# FanoutTest.net
KiCad netlist of a schematic drawn in Altium Designer
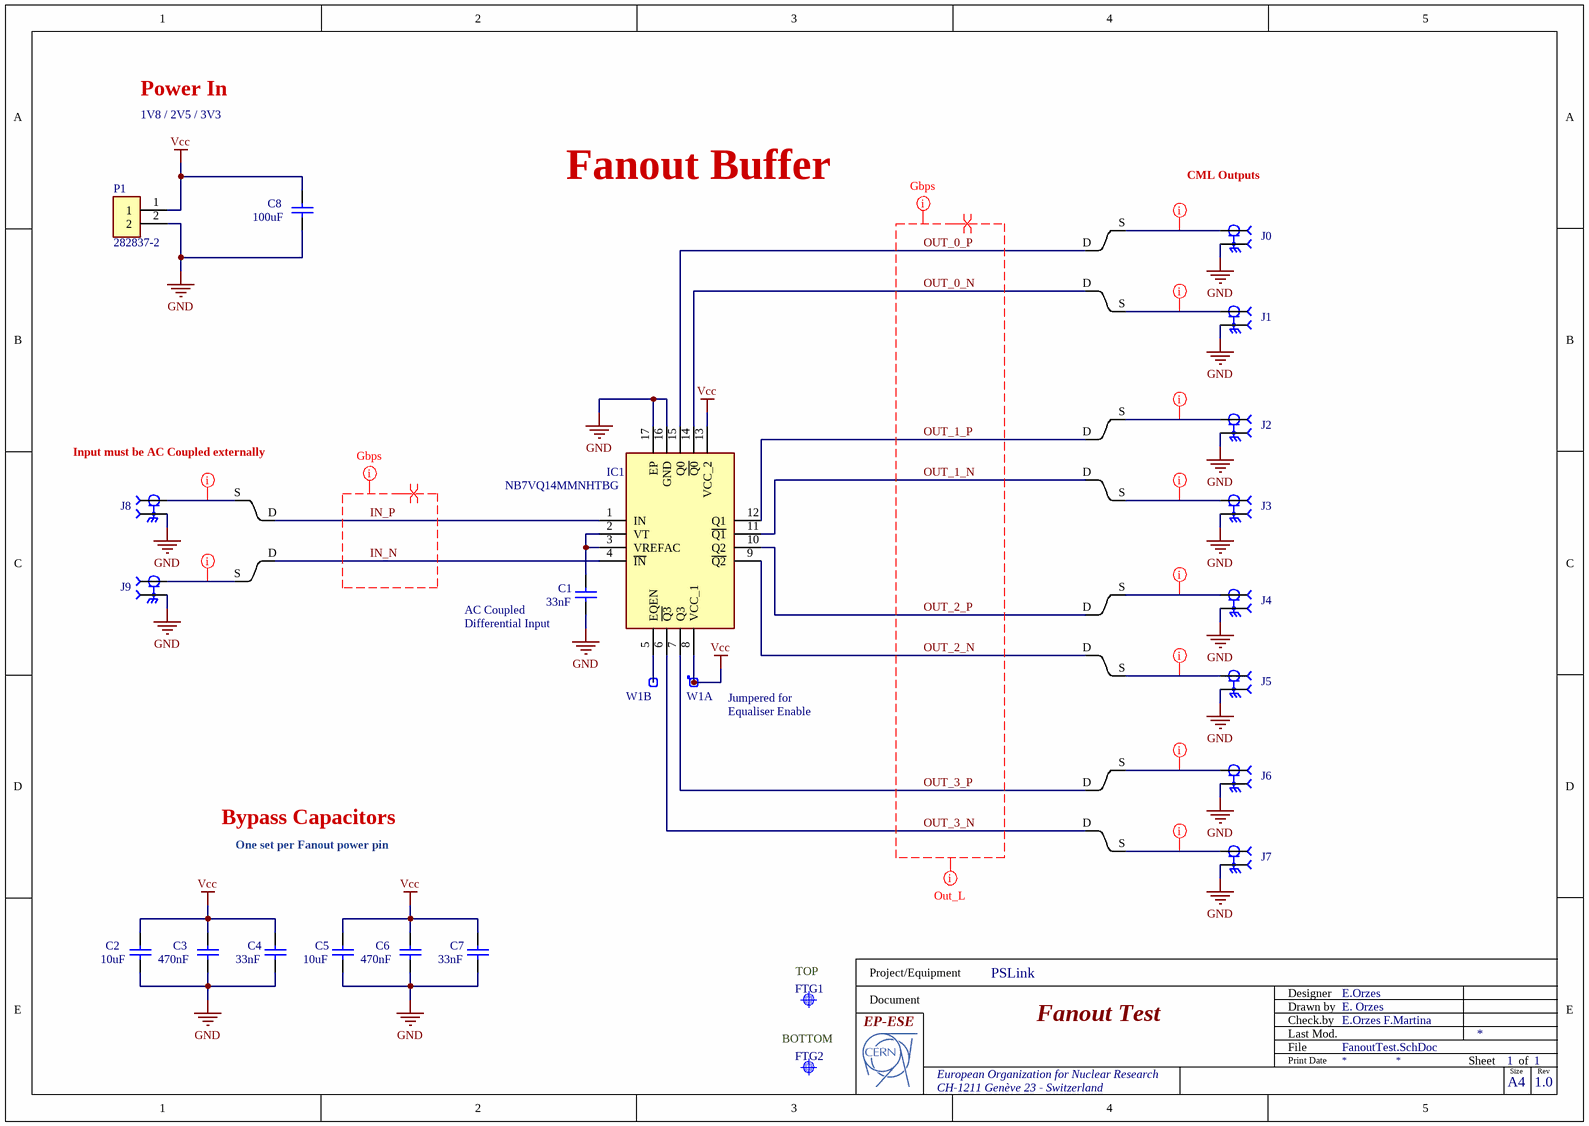
[diagram p0: FanoutTest.SchDoc]

(export (version "E")
  (design (tool "Eeschema 10.0.6"))
  (components
    (comp (ref "C1")
      (value "33nF")
      (footprint "LLL03TR61E333KE01")
      (description "LLL03TR61E333KE01")
      (libsource (lib "auxiliary_library") (part "Capacitor - non polarized"))
    )
    (comp (ref "C2")
      (value "10uF")
      (footprint "CAPC1608X87N")
      (description "GRM188D71A106KA73")
      (fields
        (field (name "PART NUMBER") "CC0603_10UF_6.3V_20%_X5R")
        (field (name "VOLTAGE") "6.3V")
        (field (name "AUTHOR") "CERN DEM JLC")
      )
      (libsource (lib "Capacitors") (part "Capacitor - non polarized"))
    )
    (comp (ref "C3")
      (value "470nF")
      (footprint "CAPC0510X04N")
      (description "LLL153C70G474ME17")
      (libsource (lib "auxiliary_library") (part "Capacitor - non polarized"))
    )
    (comp (ref "C4")
      (value "33nF")
      (footprint "LLL03TR61E333KE01")
      (description "LLL03TR61E333KE01")
      (libsource (lib "auxiliary_library") (part "Capacitor - non polarized"))
    )
    (comp (ref "C5")
      (value "10uF")
      (footprint "CAPC1608X87N")
      (description "GRM188D71A106KA73")
      (fields
        (field (name "PART NUMBER") "CC0603_10UF_6.3V_20%_X5R")
        (field (name "VOLTAGE") "6.3V")
        (field (name "AUTHOR") "CERN DEM JLC")
      )
      (libsource (lib "Capacitors") (part "Capacitor - non polarized"))
    )
    (comp (ref "C6")
      (value "470nF")
      (footprint "CAPC0510X04N")
      (description "LLL153C70G474ME17")
      (libsource (lib "auxiliary_library") (part "Capacitor - non polarized"))
    )
    (comp (ref "C7")
      (value "33nF")
      (footprint "LLL03TR61E333KE01")
      (description "LLL03TR61E333KE01")
      (libsource (lib "auxiliary_library") (part "Capacitor - non polarized"))
    )
    (comp (ref "C8")
      (value "100uF")
      (footprint "CAPC3225X270N")
      (description "GRM32EC70J107ME15")
      (fields
        (field (name "PART NUMBER") "CC1210_100UF_6.3V_20%_X7U")
        (field (name "VOLTAGE") "6.3V")
        (field (name "AUTHOR") "CERN DEM MR")
      )
      (libsource (lib "Capacitors") (part "Capacitor - non polarized"))
    )
    (comp (ref "FTG1")
      (value "Use only in PCB")
      (footprint "FIDUCIAL_TOP_C100-200")
      (description "Fiducial Target")
      (fields (field (name "PART NUMBER") "FIDUCIAL_TARGET_C100-200") (field (name "AUTHOR") "CERN DEM JLC"))
      (libsource (lib "Eletro-mechanical") (part "Fiducial Target"))
    )
    (comp (ref "FTG2")
      (value "Use only in PCB")
      (footprint "FIDUCIAL_TOP_C100-200")
      (description "Fiducial Target")
      (fields (field (name "PART NUMBER") "FIDUCIAL_TARGET_C100-200") (field (name "AUTHOR") "CERN DEM JLC"))
      (libsource (lib "Eletro-mechanical") (part "Fiducial Target"))
    )
    (comp (ref "IC1")
      (value "NB7VQ14MMNHTBG")
      (footprint "SamacSys:QFN50P300X300X100-17N")
      (description "Integrated Circuit")
      (fields (field (name "MOUSER PART NUMBER") "863-NB7VQ14MMNHTBG"))
      (libsource (lib "*") (part "NB7VQ14MMNHTBG"))
    )
    (comp (ref "J0") (value "SMA") (footprint "CONSMA022-G") (libsource (lib "CONSMA022-G") (part "SMA")))
    (comp (ref "J1") (value "SMA") (footprint "CONSMA022-G") (libsource (lib "CONSMA022-G") (part "SMA")))
    (comp (ref "J2") (value "SMA") (footprint "CONSMA022-G") (libsource (lib "CONSMA022-G") (part "SMA")))
    (comp (ref "J3") (value "SMA") (footprint "CONSMA022-G") (libsource (lib "CONSMA022-G") (part "SMA")))
    (comp (ref "J4") (value "SMA") (footprint "CONSMA022-G") (libsource (lib "CONSMA022-G") (part "SMA")))
    (comp (ref "J5") (value "SMA") (footprint "CONSMA022-G") (libsource (lib "CONSMA022-G") (part "SMA")))
    (comp (ref "J6") (value "SMA") (footprint "CONSMA022-G") (libsource (lib "CONSMA022-G") (part "SMA")))
    (comp (ref "J7") (value "SMA") (footprint "CONSMA022-G") (libsource (lib "CONSMA022-G") (part "SMA")))
    (comp (ref "J8") (value "SMA") (footprint "CONSMA022-G") (libsource (lib "CONSMA022-G") (part "SMA")))
    (comp (ref "J9") (value "SMA") (footprint "CONSMA022-G") (libsource (lib "CONSMA022-G") (part "SMA")))
    (comp (ref "P1")
      (value "282837-2")
      (footprint "TE_282837-2:TE_282837-2")
      (fields (field (name "MF") "TE Connectivity"))
      (libsource (lib "282837-2") (part "282837-2"))
    )
    (comp (ref "TA1")
      (value "Differential to Single Transition")
      (footprint "lane_width_transition")
      (libsource (lib "auxiliary_library") (part "lane_width_transition"))
    )
    (comp (ref "TA2")
      (value "Differential to Single Transition")
      (footprint "lane_width_transition")
      (libsource (lib "auxiliary_library") (part "lane_width_transition"))
    )
    (comp (ref "TA3")
      (value "Differential to Single Transition")
      (footprint "lane_width_transition")
      (libsource (lib "auxiliary_library") (part "lane_width_transition"))
    )
    (comp (ref "TA4")
      (value "Differential to Single Transition")
      (footprint "lane_width_transition")
      (libsource (lib "auxiliary_library") (part "lane_width_transition"))
    )
    (comp (ref "TA5")
      (value "Differential to Single Transition")
      (footprint "lane_width_transition")
      (libsource (lib "auxiliary_library") (part "lane_width_transition"))
    )
    (comp (ref "TA6")
      (value "Differential to Single Transition")
      (footprint "lane_width_transition")
      (libsource (lib "auxiliary_library") (part "lane_width_transition"))
    )
    (comp (ref "TA7")
      (value "Differential to Single Transition")
      (footprint "lane_width_transition")
      (libsource (lib "auxiliary_library") (part "lane_width_transition"))
    )
    (comp (ref "TA8")
      (value "Differential to Single Transition")
      (footprint "lane_width_transition")
      (libsource (lib "auxiliary_library") (part "lane_width_transition"))
    )
    (comp (ref "TA9")
      (value "Differential to Single Transition")
      (footprint "lane_width_transition")
      (libsource (lib "auxiliary_library") (part "lane_width_transition"))
    )
    (comp (ref "TA10")
      (value "Differential to Single Transition")
      (footprint "lane_width_transition")
      (libsource (lib "auxiliary_library") (part "lane_width_transition"))
    )
    (comp (ref "W1")
      (value "Header 2")
      (footprint "SAMTEC_HTSW-102-23-L-S")
      (description "2 Mini Wire-Wrap Contact Strip Header")
      (fields
        (field (name "PART NUMBER") "SAMTEC_HTSW-102-23-L-S")
        (field (name "MANUFACTURER") "SAMTEC")
        (field (name "AUTHOR") "CERN DEM JLC")
      )
      (libsource (lib "Connectors") (part "Wire-Wrap Contact x2"))
    )
  )
  (nets
    (net (code "1") (name "/IN_N") (class "Default")
      (node (ref "IC1") (pin "4") (pinfunction "~{IN}_4") (pintype "passive"))
      (node (ref "TA6") (pin "D") (pinfunction "D_D") (pintype "passive"))
    )
    (net (code "2") (name "/IN_P") (class "Default")
      (node (ref "IC1") (pin "1") (pinfunction "IN_1") (pintype "passive"))
      (node (ref "TA4") (pin "D") (pinfunction "D_D") (pintype "passive"))
    )
    (net (code "3") (name "/OUT_0_N") (class "Default")
      (node (ref "IC1") (pin "14") (pinfunction "~{Q0}_14") (pintype "passive"))
      (node (ref "TA2") (pin "D") (pinfunction "D_D") (pintype "passive"))
    )
    (net (code "4") (name "/OUT_0_P") (class "Default")
      (node (ref "IC1") (pin "15") (pinfunction "Q0_15") (pintype "passive"))
      (node (ref "TA1") (pin "D") (pinfunction "D_D") (pintype "passive"))
    )
    (net (code "5") (name "/OUT_1_N") (class "Default")
      (node (ref "IC1") (pin "11") (pinfunction "~{Q1}_11") (pintype "passive"))
      (node (ref "TA5") (pin "D") (pinfunction "D_D") (pintype "passive"))
    )
    (net (code "6") (name "/OUT_1_P") (class "Default")
      (node (ref "IC1") (pin "12") (pinfunction "Q1_12") (pintype "passive"))
      (node (ref "TA3") (pin "D") (pinfunction "D_D") (pintype "passive"))
    )
    (net (code "7") (name "/OUT_2_N") (class "Default")
      (node (ref "IC1") (pin "9") (pinfunction "~{Q2}_9") (pintype "passive"))
      (node (ref "TA8") (pin "D") (pinfunction "D_D") (pintype "passive"))
    )
    (net (code "8") (name "/OUT_2_P") (class "Default")
      (node (ref "IC1") (pin "10") (pinfunction "Q2_10") (pintype "passive"))
      (node (ref "TA7") (pin "D") (pinfunction "D_D") (pintype "passive"))
    )
    (net (code "9") (name "/OUT_3_N") (class "Default")
      (node (ref "IC1") (pin "6") (pinfunction "~{Q3}_6") (pintype "passive"))
      (node (ref "TA10") (pin "D") (pinfunction "D_D") (pintype "passive"))
    )
    (net (code "10") (name "/OUT_3_P") (class "Default")
      (node (ref "IC1") (pin "7") (pinfunction "Q3_7") (pintype "passive"))
      (node (ref "TA9") (pin "D") (pinfunction "D_D") (pintype "passive"))
    )
    (net (code "11") (name "GND") (class "Default")
      (node (ref "C1") (pin "1") (pinfunction "1_1") (pintype "passive"))
      (node (ref "C2") (pin "1") (pinfunction "1_1") (pintype "passive"))
      (node (ref "C3") (pin "1") (pinfunction "1_1") (pintype "passive"))
      (node (ref "C4") (pin "1") (pinfunction "1_1") (pintype "passive"))
      (node (ref "C5") (pin "1") (pinfunction "1_1") (pintype "passive"))
      (node (ref "C6") (pin "1") (pinfunction "1_1") (pintype "passive"))
      (node (ref "C7") (pin "1") (pinfunction "1_1") (pintype "passive"))
      (node (ref "C8") (pin "1") (pinfunction "1_1") (pintype "passive"))
      (node (ref "IC1") (pin "16") (pinfunction "GND_16") (pintype "passive"))
      (node (ref "IC1") (pin "17") (pinfunction "EP_17") (pintype "passive"))
      (node (ref "J0") (pin "0") (pinfunction "GND_0") (pintype "passive"))
      (node (ref "J1") (pin "0") (pinfunction "GND_0") (pintype "passive"))
      (node (ref "J2") (pin "0") (pinfunction "GND_0") (pintype "passive"))
      (node (ref "J3") (pin "0") (pinfunction "GND_0") (pintype "passive"))
      (node (ref "J4") (pin "0") (pinfunction "GND_0") (pintype "passive"))
      (node (ref "J5") (pin "0") (pinfunction "GND_0") (pintype "passive"))
      (node (ref "J6") (pin "0") (pinfunction "GND_0") (pintype "passive"))
      (node (ref "J7") (pin "0") (pinfunction "GND_0") (pintype "passive"))
      (node (ref "J8") (pin "0") (pinfunction "GND_0") (pintype "passive"))
      (node (ref "J9") (pin "0") (pinfunction "GND_0") (pintype "passive"))
      (node (ref "P1") (pin "2") (pinfunction "2_2") (pintype "passive"))
    )
    (net (code "12") (name "Net-(IC1-EQEN)") (class "Default")
      (node (ref "IC1") (pin "5") (pinfunction "EQEN_5") (pintype "passive"))
      (node (ref "W1") (pin "2") (pinfunction "2_2") (pintype "power_in"))
    )
    (net (code "13") (name "Net-(IC1-VREFAC)") (class "Default")
      (node (ref "C1") (pin "2") (pinfunction "2_2") (pintype "passive"))
      (node (ref "IC1") (pin "2") (pinfunction "VT_2") (pintype "passive"))
      (node (ref "IC1") (pin "3") (pinfunction "VREFAC_3") (pintype "passive"))
    )
    (net (code "14") (name "Net-(J0-S)") (class "Default")
      (node (ref "J0") (pin "1") (pinfunction "S_1") (pintype "passive"))
      (node (ref "TA1") (pin "S") (pinfunction "S_S") (pintype "passive"))
    )
    (net (code "15") (name "Net-(J1-S)") (class "Default")
      (node (ref "J1") (pin "1") (pinfunction "S_1") (pintype "passive"))
      (node (ref "TA2") (pin "S") (pinfunction "S_S") (pintype "passive"))
    )
    (net (code "16") (name "Net-(J2-S)") (class "Default")
      (node (ref "J2") (pin "1") (pinfunction "S_1") (pintype "passive"))
      (node (ref "TA3") (pin "S") (pinfunction "S_S") (pintype "passive"))
    )
    (net (code "17") (name "Net-(J3-S)") (class "Default")
      (node (ref "J3") (pin "1") (pinfunction "S_1") (pintype "passive"))
      (node (ref "TA5") (pin "S") (pinfunction "S_S") (pintype "passive"))
    )
    (net (code "18") (name "Net-(J4-S)") (class "Default")
      (node (ref "J4") (pin "1") (pinfunction "S_1") (pintype "passive"))
      (node (ref "TA7") (pin "S") (pinfunction "S_S") (pintype "passive"))
    )
    (net (code "19") (name "Net-(J5-S)") (class "Default")
      (node (ref "J5") (pin "1") (pinfunction "S_1") (pintype "passive"))
      (node (ref "TA8") (pin "S") (pinfunction "S_S") (pintype "passive"))
    )
    (net (code "20") (name "Net-(J6-S)") (class "Default")
      (node (ref "J6") (pin "1") (pinfunction "S_1") (pintype "passive"))
      (node (ref "TA9") (pin "S") (pinfunction "S_S") (pintype "passive"))
    )
    (net (code "21") (name "Net-(J7-S)") (class "Default")
      (node (ref "J7") (pin "1") (pinfunction "S_1") (pintype "passive"))
      (node (ref "TA10") (pin "S") (pinfunction "S_S") (pintype "passive"))
    )
    (net (code "22") (name "Net-(J8-S)") (class "Default")
      (node (ref "J8") (pin "1") (pinfunction "S_1") (pintype "passive"))
      (node (ref "TA4") (pin "S") (pinfunction "S_S") (pintype "passive"))
    )
    (net (code "23") (name "Net-(J9-S)") (class "Default")
      (node (ref "J9") (pin "1") (pinfunction "S_1") (pintype "passive"))
      (node (ref "TA6") (pin "S") (pinfunction "S_S") (pintype "passive"))
    )
    (net (code "24") (name "Vcc") (class "Default")
      (node (ref "C2") (pin "2") (pinfunction "2_2") (pintype "passive"))
      (node (ref "C3") (pin "2") (pinfunction "2_2") (pintype "passive"))
      (node (ref "C4") (pin "2") (pinfunction "2_2") (pintype "passive"))
      (node (ref "C5") (pin "2") (pinfunction "2_2") (pintype "passive"))
      (node (ref "C6") (pin "2") (pinfunction "2_2") (pintype "passive"))
      (node (ref "C7") (pin "2") (pinfunction "2_2") (pintype "passive"))
      (node (ref "C8") (pin "2") (pinfunction "2_2") (pintype "passive"))
      (node (ref "IC1") (pin "13") (pinfunction "VCC_2_13") (pintype "passive"))
      (node (ref "IC1") (pin "8") (pinfunction "VCC_1_8") (pintype "passive"))
      (node (ref "P1") (pin "1") (pinfunction "1_1") (pintype "passive"))
      (node (ref "W1") (pin "1") (pinfunction "1_1") (pintype "bidirectional"))
    )
  )
)
